# OSSI-1_OBC_1.net
KiCad netlist of a schematic drawn in Altium Designer
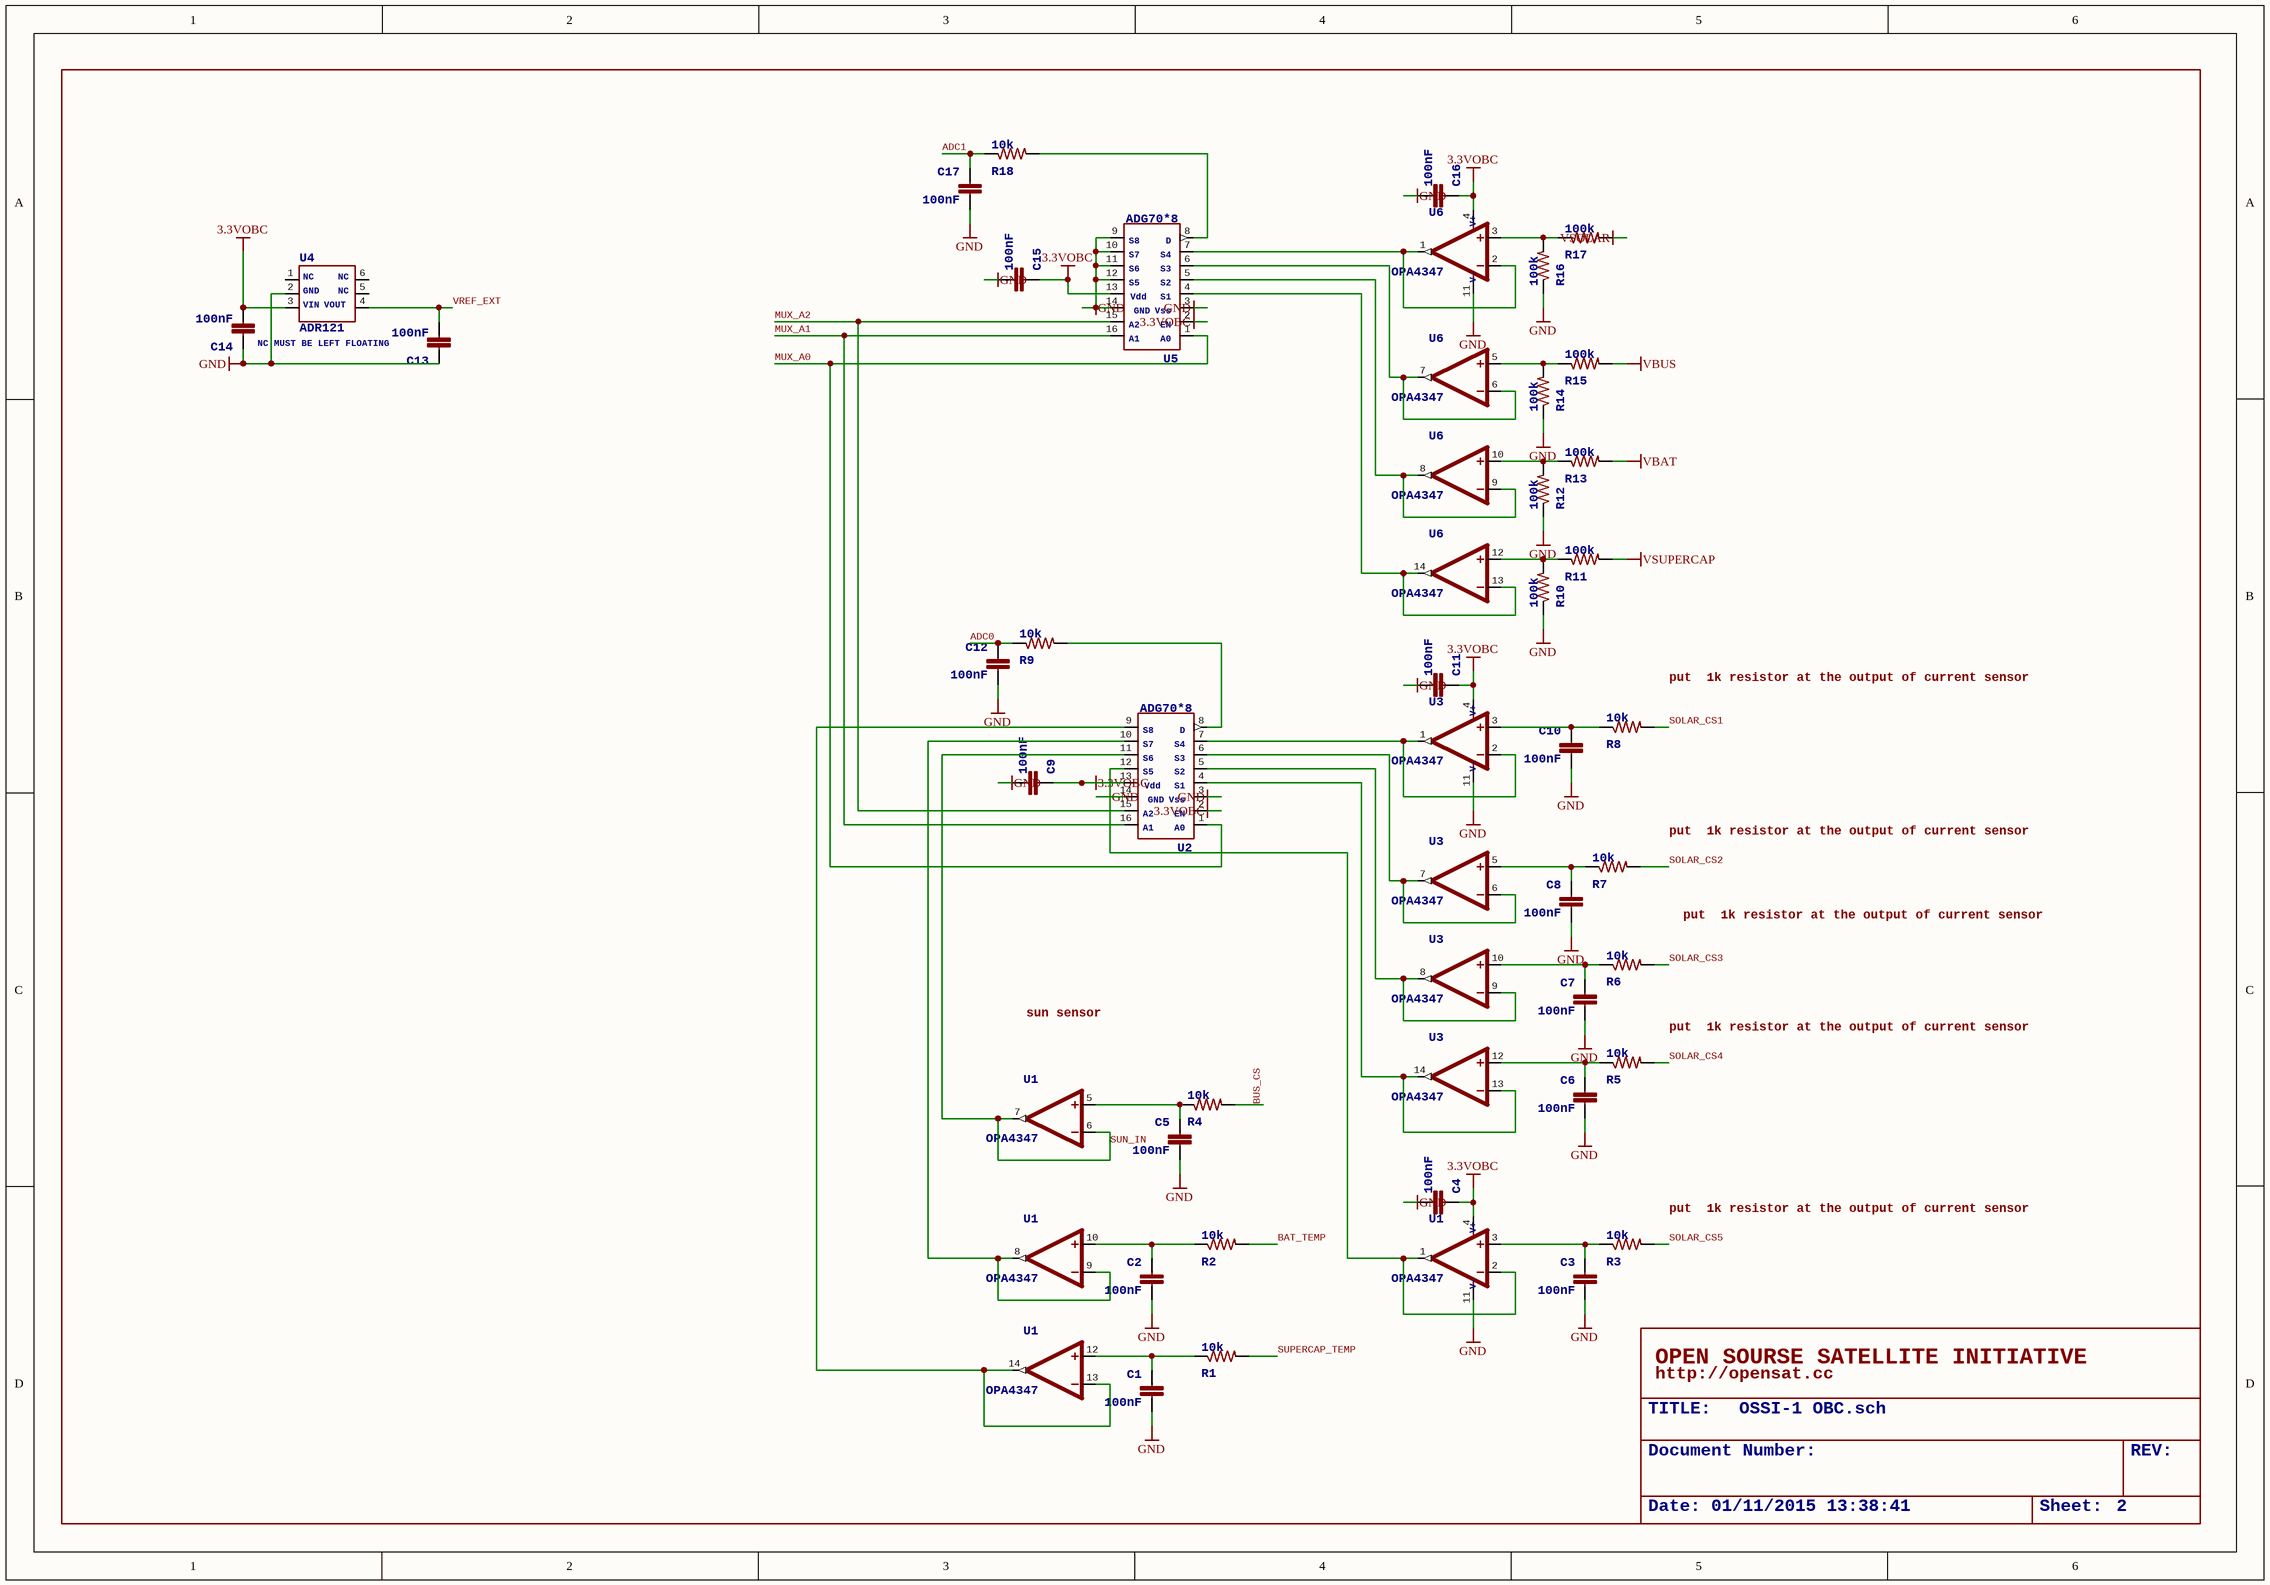
[diagram p0: OSSI-1 OBC_1.SchDoc]

(export (version "E")
  (design (tool "Eeschema 10.0.6"))
  (components
    (comp (ref "C1")
      (value "100nF")
      (footprint "C0603(1608)")
      (fields (field (name ">NAME") "C1") (field (name ">VALUE") "100nF"))
      (libsource (lib "OSSI") (part "C0603(1608)"))
    )
    (comp (ref "C2")
      (value "100nF")
      (footprint "C0603(1608)")
      (fields (field (name ">NAME") "C2") (field (name ">VALUE") "100nF"))
      (libsource (lib "OSSI") (part "C0603(1608)"))
    )
    (comp (ref "C3")
      (value "100nF")
      (footprint "C0603(1608)")
      (fields (field (name ">NAME") "C3") (field (name ">VALUE") "100nF"))
      (libsource (lib "OSSI") (part "C0603(1608)"))
    )
    (comp (ref "C4")
      (value "100nF")
      (footprint "C0603(1608)")
      (fields (field (name ">NAME") "C4") (field (name ">VALUE") "100nF"))
      (libsource (lib "") (part "C0603(1608)_1"))
    )
    (comp (ref "C5")
      (value "100nF")
      (footprint "C0603(1608)")
      (fields (field (name ">NAME") "C5") (field (name ">VALUE") "100nF"))
      (libsource (lib "OSSI") (part "C0603(1608)"))
    )
    (comp (ref "C6")
      (value "100nF")
      (footprint "C0603(1608)")
      (fields (field (name ">NAME") "C6") (field (name ">VALUE") "100nF"))
      (libsource (lib "OSSI") (part "C0603(1608)"))
    )
    (comp (ref "C7")
      (value "100nF")
      (footprint "C0603(1608)")
      (fields (field (name ">NAME") "C7") (field (name ">VALUE") "100nF"))
      (libsource (lib "OSSI") (part "C0603(1608)"))
    )
    (comp (ref "C8")
      (value "100nF")
      (footprint "C0603(1608)")
      (fields (field (name ">NAME") "C8") (field (name ">VALUE") "100nF"))
      (libsource (lib "OSSI") (part "C0603(1608)"))
    )
    (comp (ref "C9")
      (value "100nF")
      (footprint "C0603(1608)")
      (fields (field (name ">NAME") "C9") (field (name ">VALUE") "100nF"))
      (libsource (lib "") (part "C0603(1608)_1"))
    )
    (comp (ref "C10")
      (value "100nF")
      (footprint "C0603(1608)")
      (fields (field (name ">NAME") "C10") (field (name ">VALUE") "100nF"))
      (libsource (lib "OSSI") (part "C0603(1608)"))
    )
    (comp (ref "C11")
      (value "100nF")
      (footprint "C0603(1608)")
      (fields (field (name ">NAME") "C11") (field (name ">VALUE") "100nF"))
      (libsource (lib "") (part "C0603(1608)_1"))
    )
    (comp (ref "C12")
      (value "100nF")
      (footprint "C0603(1608)")
      (fields (field (name ">NAME") "C12") (field (name ">VALUE") "100nF"))
      (libsource (lib "OSSI") (part "C0603(1608)"))
    )
    (comp (ref "C13")
      (value "100nF")
      (footprint "C0603(1608)")
      (fields (field (name ">NAME") "C13") (field (name ">VALUE") "100nF"))
      (libsource (lib "") (part "C0603(1608)_2"))
    )
    (comp (ref "C14")
      (value "100nF")
      (footprint "C0603(1608)")
      (fields (field (name ">NAME") "C14") (field (name ">VALUE") "100nF"))
      (libsource (lib "") (part "C0603(1608)_2"))
    )
    (comp (ref "C15")
      (value "100nF")
      (footprint "C0603(1608)")
      (fields (field (name ">NAME") "C15") (field (name ">VALUE") "100nF"))
      (libsource (lib "") (part "C0603(1608)_1"))
    )
    (comp (ref "C16")
      (value "100nF")
      (footprint "C0603(1608)")
      (fields (field (name ">NAME") "C16") (field (name ">VALUE") "100nF"))
      (libsource (lib "") (part "C0603(1608)_1"))
    )
    (comp (ref "C17")
      (value "100nF")
      (footprint "C0603(1608)")
      (fields (field (name ">NAME") "C17") (field (name ">VALUE") "100nF"))
      (libsource (lib "OSSI") (part "C0603(1608)"))
    )
    (comp (ref "R1")
      (value "10k")
      (footprint "R0603(1608)")
      (fields (field (name ">NAME") "R1") (field (name ">VALUE") "10k"))
      (libsource (lib "OSSI") (part "R0603(1608)"))
    )
    (comp (ref "R2")
      (value "10k")
      (footprint "R0603(1608)")
      (fields (field (name ">NAME") "R2") (field (name ">VALUE") "10k"))
      (libsource (lib "OSSI") (part "R0603(1608)"))
    )
    (comp (ref "R3")
      (value "10k")
      (footprint "R0603(1608)")
      (fields (field (name ">NAME") "R3") (field (name ">VALUE") "10k"))
      (libsource (lib "OSSI") (part "R0603(1608)"))
    )
    (comp (ref "R4")
      (value "10k")
      (footprint "R0603(1608)")
      (fields (field (name ">NAME") "R4") (field (name ">VALUE") "10k"))
      (libsource (lib "OSSI") (part "R0603(1608)"))
    )
    (comp (ref "R5")
      (value "10k")
      (footprint "R0603(1608)")
      (fields (field (name ">NAME") "R5") (field (name ">VALUE") "10k"))
      (libsource (lib "OSSI") (part "R0603(1608)"))
    )
    (comp (ref "R6")
      (value "10k")
      (footprint "R0603(1608)")
      (fields (field (name ">NAME") "R6") (field (name ">VALUE") "10k"))
      (libsource (lib "OSSI") (part "R0603(1608)"))
    )
    (comp (ref "R7")
      (value "10k")
      (footprint "R0603(1608)")
      (fields (field (name ">NAME") "R7") (field (name ">VALUE") "10k"))
      (libsource (lib "OSSI") (part "R0603(1608)"))
    )
    (comp (ref "R8")
      (value "10k")
      (footprint "R0603(1608)")
      (fields (field (name ">NAME") "R8") (field (name ">VALUE") "10k"))
      (libsource (lib "OSSI") (part "R0603(1608)"))
    )
    (comp (ref "R9")
      (value "10k")
      (footprint "R0603(1608)")
      (fields (field (name ">NAME") "R9") (field (name ">VALUE") "10k"))
      (libsource (lib "OSSI") (part "R0603(1608)"))
    )
    (comp (ref "R10")
      (value "100k")
      (footprint "R0603(1608)")
      (fields (field (name ">NAME") "R10") (field (name ">VALUE") "100k"))
      (libsource (lib "OSSI") (part "R0603(1608)"))
    )
    (comp (ref "R11")
      (value "100k")
      (footprint "R0603(1608)")
      (fields (field (name ">NAME") "R11") (field (name ">VALUE") "100k"))
      (libsource (lib "OSSI") (part "R0603(1608)"))
    )
    (comp (ref "R12")
      (value "100k")
      (footprint "R0603(1608)")
      (fields (field (name ">NAME") "R12") (field (name ">VALUE") "100k"))
      (libsource (lib "OSSI") (part "R0603(1608)"))
    )
    (comp (ref "R13")
      (value "100k")
      (footprint "R0603(1608)")
      (fields (field (name ">NAME") "R13") (field (name ">VALUE") "100k"))
      (libsource (lib "OSSI") (part "R0603(1608)"))
    )
    (comp (ref "R14")
      (value "100k")
      (footprint "R0603(1608)")
      (fields (field (name ">NAME") "R14") (field (name ">VALUE") "100k"))
      (libsource (lib "OSSI") (part "R0603(1608)"))
    )
    (comp (ref "R15")
      (value "100k")
      (footprint "R0603(1608)")
      (fields (field (name ">NAME") "R15") (field (name ">VALUE") "100k"))
      (libsource (lib "OSSI") (part "R0603(1608)"))
    )
    (comp (ref "R16")
      (value "100k")
      (footprint "R0603(1608)")
      (fields (field (name ">NAME") "R16") (field (name ">VALUE") "100k"))
      (libsource (lib "OSSI") (part "R0603(1608)"))
    )
    (comp (ref "R17")
      (value "100k")
      (footprint "R0603(1608)")
      (fields (field (name ">NAME") "R17") (field (name ">VALUE") "100k"))
      (libsource (lib "OSSI") (part "R0603(1608)"))
    )
    (comp (ref "R18")
      (value "10k")
      (footprint "R0603(1608)")
      (fields (field (name ">NAME") "R18") (field (name ">VALUE") "10k"))
      (libsource (lib "OSSI") (part "R0603(1608)"))
    )
    (comp (ref "U1")
      (value "OPA4347")
      (footprint "TSSOP14-PW")
      (fields
        (field (name ">NAME") "U1")
        (field (name ">VALUE") "OPA4347")
        (field (name "V+") "V+")
        (field (name "V-") "V-")
      )
      (libsource (lib "OSSI") (part "OPA4347"))
    )
    (comp (ref "U2")
      (value "ADG70*8")
      (footprint "TSSOP16-RU")
      (fields
        (field (name "A0") "A0")
        (field (name "EN") "EN")
        (field (name "VSS") "Vss")
        (field (name "S1") "S1")
        (field (name "S2") "S2")
        (field (name "S3") "S3")
        (field (name "S4") "S4")
        (field (name "D") "D")
        (field (name "S5") "S5")
        (field (name "S6") "S6")
        (field (name "S7") "S7")
        (field (name "S8") "S8")
        (field (name "VDD") "Vdd")
        (field (name "GND") "GND")
        (field (name "A2") "A2")
        (field (name "A1") "A1")
        (field (name ">NAME") "U2")
        (field (name ">VALUE") "ADG70*8")
      )
      (libsource (lib "OSSI") (part "ADG70*8"))
    )
    (comp (ref "U3")
      (value "OPA4347")
      (footprint "TSSOP14-PW")
      (fields
        (field (name ">NAME") "U3")
        (field (name ">VALUE") "OPA4347")
        (field (name "V+") "V+")
        (field (name "V-") "V-")
      )
      (libsource (lib "OSSI") (part "OPA4347"))
    )
    (comp (ref "U4")
      (value "ADR121")
      (footprint "TSOT-6UJ-6")
      (description "ADR127<br/>\nPrecision, Micropower LDO Voltage\nReferences in TSOT\n<br/>ADR127BUJZ-REEL7")
      (fields
        (field (name ">NAME") "U4")
        (field (name ">VALUE") "ADR121")
        (field (name "NC") "NC")
        (field (name "GND") "GND")
        (field (name "VIN") "VIN")
        (field (name "VOUT") "VOUT")
        (field (name "NC_1") "NC")
        (field (name "NC_2") "NC")
        (field (name "NC MUST BE LEFT FLOATING") "NC MUST BE LEFT FLOATING")
      )
      (libsource (lib "OSSI") (part "ADR127BUJZ-REEL7"))
    )
    (comp (ref "U5")
      (value "ADG70*8")
      (footprint "TSSOP16-RU")
      (fields
        (field (name "A0") "A0")
        (field (name "EN") "EN")
        (field (name "VSS") "Vss")
        (field (name "S1") "S1")
        (field (name "S2") "S2")
        (field (name "S3") "S3")
        (field (name "S4") "S4")
        (field (name "D") "D")
        (field (name "S5") "S5")
        (field (name "S6") "S6")
        (field (name "S7") "S7")
        (field (name "S8") "S8")
        (field (name "VDD") "Vdd")
        (field (name "GND") "GND")
        (field (name "A2") "A2")
        (field (name "A1") "A1")
        (field (name ">NAME") "U5")
        (field (name ">VALUE") "ADG70*8")
      )
      (libsource (lib "OSSI") (part "ADG70*8"))
    )
    (comp (ref "U6")
      (value "OPA4347")
      (footprint "TSSOP14-PW")
      (fields
        (field (name ">NAME") "U6")
        (field (name ">VALUE") "OPA4347")
        (field (name "V+") "V+")
        (field (name "V-") "V-")
      )
      (libsource (lib "OSSI") (part "OPA4347"))
    )
  )
  (nets
    (net (code "1") (name "/ADC0") (class "Default")
      (node (ref "C12") (pin "1") (pinfunction "1_1") (pintype "passive"))
      (node (ref "R9") (pin "1") (pinfunction "1_1") (pintype "passive"))
    )
    (net (code "2") (name "/ADC1") (class "Default")
      (node (ref "C17") (pin "1") (pinfunction "1_1") (pintype "passive"))
      (node (ref "R18") (pin "1") (pinfunction "1_1") (pintype "passive"))
    )
    (net (code "3") (name "/BAT_TEMP") (class "Default")
      (node (ref "R2") (pin "2") (pinfunction "2_2") (pintype "passive"))
    )
    (net (code "4") (name "/BUS_CS") (class "Default")
      (node (ref "R4") (pin "2") (pinfunction "2_2") (pintype "passive"))
    )
    (net (code "5") (name "/MUX_A0") (class "Default")
      (node (ref "U2") (pin "1") (pinfunction "P$1_1") (pintype "passive"))
      (node (ref "U5") (pin "1") (pinfunction "P$1_1") (pintype "passive"))
    )
    (net (code "6") (name "/MUX_A1") (class "Default")
      (node (ref "U2") (pin "16") (pinfunction "P$16_16") (pintype "passive"))
      (node (ref "U5") (pin "16") (pinfunction "P$16_16") (pintype "passive"))
    )
    (net (code "7") (name "/MUX_A2") (class "Default")
      (node (ref "U2") (pin "15") (pinfunction "P$15_15") (pintype "passive"))
      (node (ref "U5") (pin "15") (pinfunction "P$15_15") (pintype "passive"))
    )
    (net (code "8") (name "/SOLAR_CS1") (class "Default")
      (node (ref "R8") (pin "2") (pinfunction "2_2") (pintype "passive"))
    )
    (net (code "9") (name "/SOLAR_CS2") (class "Default")
      (node (ref "R7") (pin "2") (pinfunction "2_2") (pintype "passive"))
    )
    (net (code "10") (name "/SOLAR_CS3") (class "Default")
      (node (ref "R6") (pin "2") (pinfunction "2_2") (pintype "passive"))
    )
    (net (code "11") (name "/SOLAR_CS4") (class "Default")
      (node (ref "R5") (pin "2") (pinfunction "2_2") (pintype "passive"))
    )
    (net (code "12") (name "/SOLAR_CS5") (class "Default")
      (node (ref "R3") (pin "2") (pinfunction "2_2") (pintype "passive"))
    )
    (net (code "13") (name "/SUN_IN") (class "Default")
      (node (ref "U1") (pin "6") (pinfunction "-IN_6") (pintype "passive"))
      (node (ref "U1") (pin "7") (pinfunction "OUT_7") (pintype "output"))
      (node (ref "U2") (pin "11") (pinfunction "P$11_11") (pintype "passive"))
    )
    (net (code "14") (name "/SUPERCAP_TEMP") (class "Default")
      (node (ref "R1") (pin "2") (pinfunction "2_2") (pintype "passive"))
    )
    (net (code "15") (name "/VREF_EXT") (class "Default")
      (node (ref "C13") (pin "2") (pinfunction "2_2") (pintype "passive"))
      (node (ref "U4") (pin "4") (pinfunction "P$4_4") (pintype "passive"))
    )
    (net (code "16") (name "3.3VOBC") (class "Default")
      (node (ref "C11") (pin "1") (pinfunction "1_1") (pintype "passive"))
      (node (ref "C14") (pin "2") (pinfunction "2_2") (pintype "passive"))
      (node (ref "C15") (pin "1") (pinfunction "1_1") (pintype "passive"))
      (node (ref "C16") (pin "1") (pinfunction "1_1") (pintype "passive"))
      (node (ref "C4") (pin "1") (pinfunction "1_1") (pintype "passive"))
      (node (ref "C9") (pin "1") (pinfunction "1_1") (pintype "passive"))
      (node (ref "U1") (pin "4") (pinfunction "V+_4") (pintype "power_in"))
      (node (ref "U2") (pin "13") (pinfunction "P$13_13") (pintype "power_in"))
      (node (ref "U2") (pin "2") (pinfunction "P$2_2") (pintype "passive"))
      (node (ref "U3") (pin "4") (pinfunction "V+_4") (pintype "power_in"))
      (node (ref "U4") (pin "3") (pinfunction "P$3_3") (pintype "passive"))
      (node (ref "U5") (pin "13") (pinfunction "P$13_13") (pintype "power_in"))
      (node (ref "U5") (pin "2") (pinfunction "P$2_2") (pintype "passive"))
      (node (ref "U6") (pin "4") (pinfunction "V+_4") (pintype "power_in"))
    )
    (net (code "17") (name "GND") (class "Default")
      (node (ref "C1") (pin "2") (pinfunction "2_2") (pintype "passive"))
      (node (ref "C10") (pin "2") (pinfunction "2_2") (pintype "passive"))
      (node (ref "C11") (pin "2") (pinfunction "2_2") (pintype "passive"))
      (node (ref "C12") (pin "2") (pinfunction "2_2") (pintype "passive"))
      (node (ref "C13") (pin "1") (pinfunction "1_1") (pintype "passive"))
      (node (ref "C14") (pin "1") (pinfunction "1_1") (pintype "passive"))
      (node (ref "C15") (pin "2") (pinfunction "2_2") (pintype "passive"))
      (node (ref "C16") (pin "2") (pinfunction "2_2") (pintype "passive"))
      (node (ref "C17") (pin "2") (pinfunction "2_2") (pintype "passive"))
      (node (ref "C2") (pin "2") (pinfunction "2_2") (pintype "passive"))
      (node (ref "C3") (pin "2") (pinfunction "2_2") (pintype "passive"))
      (node (ref "C4") (pin "2") (pinfunction "2_2") (pintype "passive"))
      (node (ref "C5") (pin "2") (pinfunction "2_2") (pintype "passive"))
      (node (ref "C6") (pin "2") (pinfunction "2_2") (pintype "passive"))
      (node (ref "C7") (pin "2") (pinfunction "2_2") (pintype "passive"))
      (node (ref "C8") (pin "2") (pinfunction "2_2") (pintype "passive"))
      (node (ref "C9") (pin "2") (pinfunction "2_2") (pintype "passive"))
      (node (ref "R10") (pin "1") (pinfunction "1_1") (pintype "passive"))
      (node (ref "R12") (pin "1") (pinfunction "1_1") (pintype "passive"))
      (node (ref "R14") (pin "1") (pinfunction "1_1") (pintype "passive"))
      (node (ref "R16") (pin "1") (pinfunction "1_1") (pintype "passive"))
      (node (ref "U1") (pin "11") (pinfunction "V-_11") (pintype "power_in"))
      (node (ref "U2") (pin "14") (pinfunction "P$14_14") (pintype "power_in"))
      (node (ref "U2") (pin "3") (pinfunction "P$3_3") (pintype "power_in"))
      (node (ref "U3") (pin "11") (pinfunction "V-_11") (pintype "power_in"))
      (node (ref "U4") (pin "2") (pinfunction "P$2_2") (pintype "passive"))
      (node (ref "U5") (pin "10") (pinfunction "P$10_10") (pintype "passive"))
      (node (ref "U5") (pin "11") (pinfunction "P$11_11") (pintype "passive"))
      (node (ref "U5") (pin "12") (pinfunction "P$12_12") (pintype "passive"))
      (node (ref "U5") (pin "14") (pinfunction "P$14_14") (pintype "power_in"))
      (node (ref "U5") (pin "3") (pinfunction "P$3_3") (pintype "power_in"))
      (node (ref "U5") (pin "9") (pinfunction "P$9_9") (pintype "passive"))
      (node (ref "U6") (pin "11") (pinfunction "V-_11") (pintype "power_in"))
    )
    (net (code "18") (name "Net-(U1A-+IN)") (class "Default")
      (node (ref "C3") (pin "1") (pinfunction "1_1") (pintype "passive"))
      (node (ref "R3") (pin "1") (pinfunction "1_1") (pintype "passive"))
      (node (ref "U1") (pin "3") (pinfunction "+IN_3") (pintype "passive"))
    )
    (net (code "19") (name "Net-(U1A--IN)") (class "Default")
      (node (ref "U1") (pin "1") (pinfunction "OUT_1") (pintype "output"))
      (node (ref "U1") (pin "2") (pinfunction "-IN_2") (pintype "passive"))
      (node (ref "U2") (pin "12") (pinfunction "P$12_12") (pintype "passive"))
    )
    (net (code "20") (name "Net-(U1B-+IN)") (class "Default")
      (node (ref "C5") (pin "1") (pinfunction "1_1") (pintype "passive"))
      (node (ref "R4") (pin "1") (pinfunction "1_1") (pintype "passive"))
      (node (ref "U1") (pin "5") (pinfunction "+IN_5") (pintype "passive"))
    )
    (net (code "21") (name "Net-(U1C-+IN)") (class "Default")
      (node (ref "C2") (pin "1") (pinfunction "1_1") (pintype "passive"))
      (node (ref "R2") (pin "1") (pinfunction "1_1") (pintype "passive"))
      (node (ref "U1") (pin "10") (pinfunction "+IN_10") (pintype "passive"))
    )
    (net (code "22") (name "Net-(U1C--IN)") (class "Default")
      (node (ref "U1") (pin "8") (pinfunction "OUT_8") (pintype "output"))
      (node (ref "U1") (pin "9") (pinfunction "-IN_9") (pintype "passive"))
      (node (ref "U2") (pin "10") (pinfunction "P$10_10") (pintype "passive"))
    )
    (net (code "23") (name "Net-(U1D-+IN)") (class "Default")
      (node (ref "C1") (pin "1") (pinfunction "1_1") (pintype "passive"))
      (node (ref "R1") (pin "1") (pinfunction "1_1") (pintype "passive"))
      (node (ref "U1") (pin "12") (pinfunction "+IN_12") (pintype "passive"))
    )
    (net (code "24") (name "Net-(U1D--IN)") (class "Default")
      (node (ref "U1") (pin "13") (pinfunction "-IN_13") (pintype "passive"))
      (node (ref "U1") (pin "14") (pinfunction "OUT_14") (pintype "output"))
      (node (ref "U2") (pin "9") (pinfunction "P$9_9") (pintype "passive"))
    )
    (net (code "25") (name "Net-(U2-P$4)") (class "Default")
      (node (ref "U2") (pin "4") (pinfunction "P$4_4") (pintype "passive"))
      (node (ref "U3") (pin "13") (pinfunction "-IN_13") (pintype "passive"))
      (node (ref "U3") (pin "14") (pinfunction "OUT_14") (pintype "output"))
    )
    (net (code "26") (name "Net-(U2-P$5)") (class "Default")
      (node (ref "U2") (pin "5") (pinfunction "P$5_5") (pintype "passive"))
      (node (ref "U3") (pin "8") (pinfunction "OUT_8") (pintype "output"))
      (node (ref "U3") (pin "9") (pinfunction "-IN_9") (pintype "passive"))
    )
    (net (code "27") (name "Net-(U2-P$6)") (class "Default")
      (node (ref "U2") (pin "6") (pinfunction "P$6_6") (pintype "passive"))
      (node (ref "U3") (pin "6") (pinfunction "-IN_6") (pintype "passive"))
      (node (ref "U3") (pin "7") (pinfunction "OUT_7") (pintype "output"))
    )
    (net (code "28") (name "Net-(U2-P$7)") (class "Default")
      (node (ref "U2") (pin "7") (pinfunction "P$7_7") (pintype "passive"))
      (node (ref "U3") (pin "1") (pinfunction "OUT_1") (pintype "output"))
      (node (ref "U3") (pin "2") (pinfunction "-IN_2") (pintype "passive"))
    )
    (net (code "29") (name "Net-(U2-P$8)") (class "Default")
      (node (ref "R9") (pin "2") (pinfunction "2_2") (pintype "passive"))
      (node (ref "U2") (pin "8") (pinfunction "P$8_8") (pintype "output"))
    )
    (net (code "30") (name "Net-(U3A-+IN)") (class "Default")
      (node (ref "C10") (pin "1") (pinfunction "1_1") (pintype "passive"))
      (node (ref "R8") (pin "1") (pinfunction "1_1") (pintype "passive"))
      (node (ref "U3") (pin "3") (pinfunction "+IN_3") (pintype "passive"))
    )
    (net (code "31") (name "Net-(U3B-+IN)") (class "Default")
      (node (ref "C8") (pin "1") (pinfunction "1_1") (pintype "passive"))
      (node (ref "R7") (pin "1") (pinfunction "1_1") (pintype "passive"))
      (node (ref "U3") (pin "5") (pinfunction "+IN_5") (pintype "passive"))
    )
    (net (code "32") (name "Net-(U3C-+IN)") (class "Default")
      (node (ref "C7") (pin "1") (pinfunction "1_1") (pintype "passive"))
      (node (ref "R6") (pin "1") (pinfunction "1_1") (pintype "passive"))
      (node (ref "U3") (pin "10") (pinfunction "+IN_10") (pintype "passive"))
    )
    (net (code "33") (name "Net-(U3D-+IN)") (class "Default")
      (node (ref "C6") (pin "1") (pinfunction "1_1") (pintype "passive"))
      (node (ref "R5") (pin "1") (pinfunction "1_1") (pintype "passive"))
      (node (ref "U3") (pin "12") (pinfunction "+IN_12") (pintype "passive"))
    )
    (net (code "34") (name "Net-(U5-P$4)") (class "Default")
      (node (ref "U5") (pin "4") (pinfunction "P$4_4") (pintype "passive"))
      (node (ref "U6") (pin "13") (pinfunction "-IN_13") (pintype "passive"))
      (node (ref "U6") (pin "14") (pinfunction "OUT_14") (pintype "output"))
    )
    (net (code "35") (name "Net-(U5-P$5)") (class "Default")
      (node (ref "U5") (pin "5") (pinfunction "P$5_5") (pintype "passive"))
      (node (ref "U6") (pin "8") (pinfunction "OUT_8") (pintype "output"))
      (node (ref "U6") (pin "9") (pinfunction "-IN_9") (pintype "passive"))
    )
    (net (code "36") (name "Net-(U5-P$6)") (class "Default")
      (node (ref "U5") (pin "6") (pinfunction "P$6_6") (pintype "passive"))
      (node (ref "U6") (pin "6") (pinfunction "-IN_6") (pintype "passive"))
      (node (ref "U6") (pin "7") (pinfunction "OUT_7") (pintype "output"))
    )
    (net (code "37") (name "Net-(U5-P$7)") (class "Default")
      (node (ref "U5") (pin "7") (pinfunction "P$7_7") (pintype "passive"))
      (node (ref "U6") (pin "1") (pinfunction "OUT_1") (pintype "output"))
      (node (ref "U6") (pin "2") (pinfunction "-IN_2") (pintype "passive"))
    )
    (net (code "38") (name "Net-(U5-P$8)") (class "Default")
      (node (ref "R18") (pin "2") (pinfunction "2_2") (pintype "passive"))
      (node (ref "U5") (pin "8") (pinfunction "P$8_8") (pintype "output"))
    )
    (net (code "39") (name "Net-(U6A-+IN)") (class "Default")
      (node (ref "R16") (pin "2") (pinfunction "2_2") (pintype "passive"))
      (node (ref "R17") (pin "1") (pinfunction "1_1") (pintype "passive"))
      (node (ref "U6") (pin "3") (pinfunction "+IN_3") (pintype "passive"))
    )
    (net (code "40") (name "Net-(U6B-+IN)") (class "Default")
      (node (ref "R14") (pin "2") (pinfunction "2_2") (pintype "passive"))
      (node (ref "R15") (pin "1") (pinfunction "1_1") (pintype "passive"))
      (node (ref "U6") (pin "5") (pinfunction "+IN_5") (pintype "passive"))
    )
    (net (code "41") (name "Net-(U6C-+IN)") (class "Default")
      (node (ref "R12") (pin "2") (pinfunction "2_2") (pintype "passive"))
      (node (ref "R13") (pin "1") (pinfunction "1_1") (pintype "passive"))
      (node (ref "U6") (pin "10") (pinfunction "+IN_10") (pintype "passive"))
    )
    (net (code "42") (name "Net-(U6D-+IN)") (class "Default")
      (node (ref "R10") (pin "2") (pinfunction "2_2") (pintype "passive"))
      (node (ref "R11") (pin "1") (pinfunction "1_1") (pintype "passive"))
      (node (ref "U6") (pin "12") (pinfunction "+IN_12") (pintype "passive"))
    )
    (net (code "43") (name "VBAT") (class "Default")
      (node (ref "R13") (pin "2") (pinfunction "2_2") (pintype "passive"))
    )
    (net (code "44") (name "VBUS") (class "Default")
      (node (ref "R15") (pin "2") (pinfunction "2_2") (pintype "passive"))
    )
    (net (code "45") (name "VSOLAR") (class "Default")
      (node (ref "R17") (pin "2") (pinfunction "2_2") (pintype "passive"))
    )
    (net (code "46") (name "VSUPERCAP") (class "Default")
      (node (ref "R11") (pin "2") (pinfunction "2_2") (pintype "passive"))
    )
    (net (code "47") (name "unconnected-(U4-P$1-Pad1)") (class "Default")
      (node (ref "U4") (pin "1") (pinfunction "P$1_1") (pintype "passive"))
    )
    (net (code "48") (name "unconnected-(U4-P$5-Pad5)") (class "Default")
      (node (ref "U4") (pin "5") (pinfunction "P$5_5") (pintype "passive"))
    )
    (net (code "49") (name "unconnected-(U4-P$6-Pad6)") (class "Default")
      (node (ref "U4") (pin "6") (pinfunction "P$6_6") (pintype "passive"))
    )
  )
)
